# Sheet1.net
KiCad netlist of a schematic drawn in Altium Designer
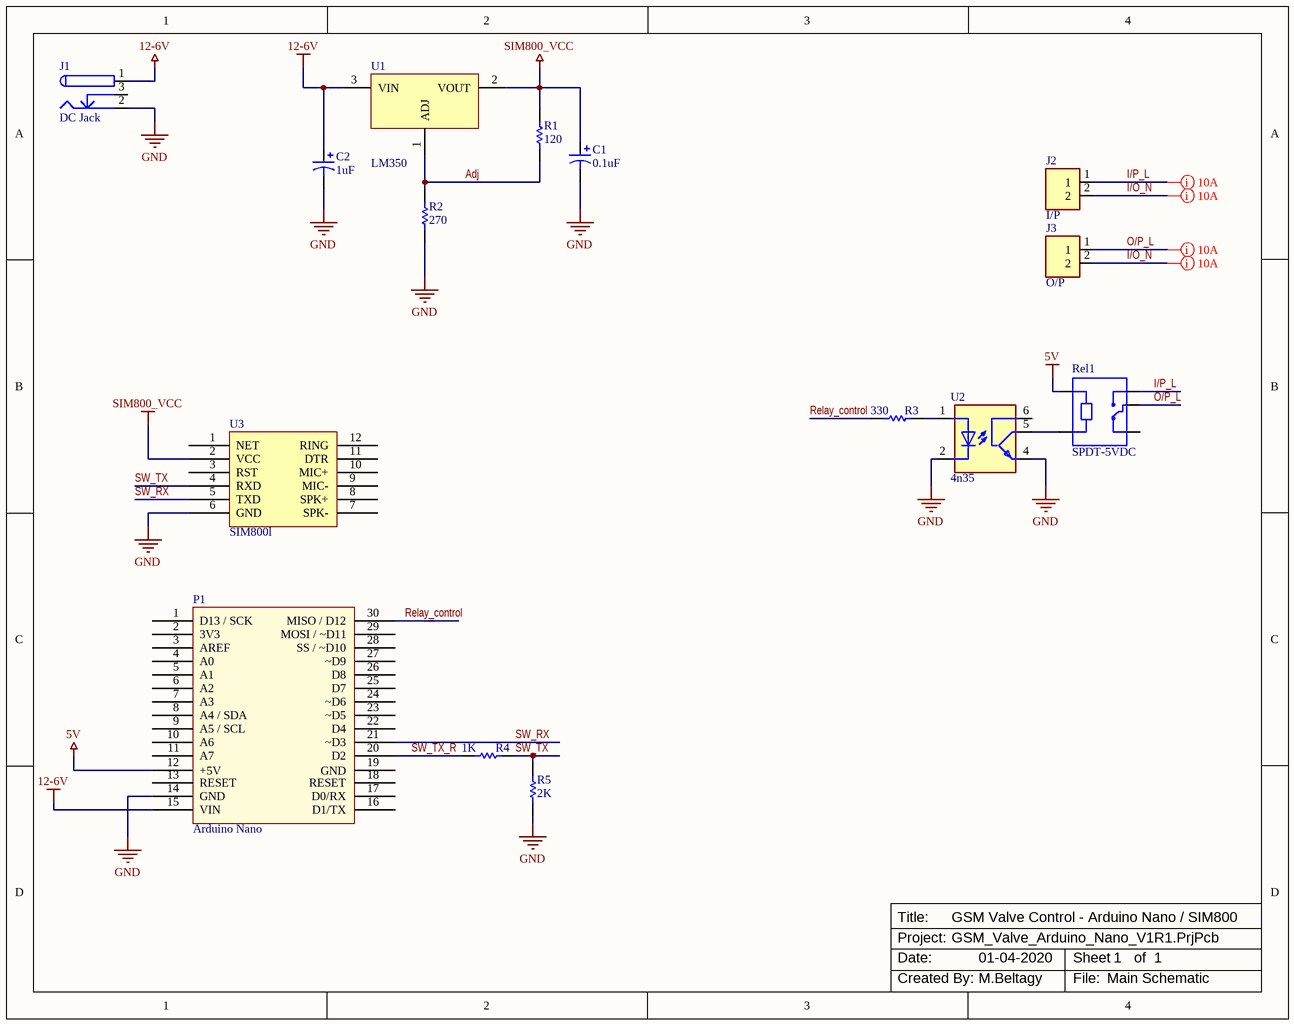
[diagram p0: Sheet1.SchDoc]

(export (version "E")
  (design (tool "Eeschema 10.0.6"))
  (components
    (comp (ref "C1")
      (value "0.1uF")
      (footprint "R38")
      (description "Polarized Capacitor (Radial)")
      (fields (field (name "PUBLISHER") "Altium Limited"))
      (libsource (lib "Miscellaneous Devices") (part "Cap Pol1"))
    )
    (comp (ref "C2")
      (value "1uF")
      (footprint "R38")
      (description "Polarized Capacitor (Radial)")
      (fields (field (name "PUBLISHER") "Altium Limited"))
      (libsource (lib "Miscellaneous Devices") (part "Cap Pol1"))
    )
    (comp (ref "J1")
      (value "DC Jack")
      (footprint "DC Jack - KLDHCX")
      (fields
        (field (name "MANUFACTURER") "Kycon")
        (field (name "MANUFACTURER PART NUMBER") "KLDHCX-0202-AC-1")
      )
      (libsource (lib "Belle_library") (part "DC Jack"))
    )
    (comp (ref "J2")
      (value "I/P")
      (footprint "Terminal Block - 2")
      (description "Terminal Block - 2 Positions")
      (fields
        (field (name "MANUFACTURER") "CUI")
        (field (name "MANUFACTURER PART NUMBER") "TBP01P1-508-02BE")
      )
      (libsource (lib "Belle_library") (part "TBP01P1-508-02BE"))
    )
    (comp (ref "J3")
      (value "O/P")
      (footprint "Terminal Block - 2")
      (description "Terminal Block - 2 Positions")
      (fields
        (field (name "MANUFACTURER") "CUI")
        (field (name "MANUFACTURER PART NUMBER") "TBP01P1-508-02BE")
      )
      (libsource (lib "Belle_library") (part "TBP01P1-508-02BE"))
    )
    (comp (ref "P1")
      (value "Arduino Nano")
      (footprint "Arduino Nano")
      (fields (field (name "MANUFACTURER") "Arduino"))
      (libsource (lib "Arduino") (part "Arduino Nano"))
    )
    (comp (ref "R1")
      (value "120")
      (footprint "AXIAL-0.5")
      (description "Semiconductor Resistor")
      (libsource (lib "Miscellaneous Devices") (part "Res Semi"))
    )
    (comp (ref "R2")
      (value "270")
      (footprint "AXIAL-0.5")
      (description "Semiconductor Resistor")
      (libsource (lib "Miscellaneous Devices") (part "Res Semi"))
    )
    (comp (ref "R3")
      (value "330")
      (footprint "AXIAL-0.5")
      (description "Semiconductor Resistor")
      (libsource (lib "Miscellaneous Devices") (part "Res Semi"))
    )
    (comp (ref "R4")
      (value "1K")
      (footprint "AXIAL-0.5")
      (description "Semiconductor Resistor")
      (libsource (lib "Miscellaneous Devices") (part "Res Semi"))
    )
    (comp (ref "R5")
      (value "2K")
      (footprint "AXIAL-0.5")
      (description "Semiconductor Resistor")
      (libsource (lib "Miscellaneous Devices") (part "Res Semi"))
    )
    (comp (ref "Rel1")
      (value "SPDT-5VDC")
      (footprint "SRD-5VDC")
      (libsource (lib "Belle_library") (part "Relay-SRD-5VDC"))
    )
    (comp (ref "U1")
      (value "LM350")
      (footprint "TO254P1054X470X1955-3")
      (fields
        (field (name "MANUFACTURER") "TI National Semiconductor")
        (field (name "MANUFACTURER PART NUMBER") "LM350AT/NOPB")
      )
      (libsource (lib "Belle_library") (part "LM350"))
    )
    (comp (ref "U2")
      (value "4n35")
      (footprint "DIP6")
      (fields (field (name "MANUFACTURER") "Everlight") (field (name "MANUFACTURER PART NUMBER") "4N35"))
      (libsource (lib "Belle_library") (part "4N35"))
    )
    (comp (ref "U3")
      (value "SIM800l")
      (footprint "SIM800l")
      (fields (field (name "MANUFACTURER PART NUMBER") "SIM800l Breakout"))
      (libsource (lib "Belle_library") (part "SIM800l"))
    )
  )
  (nets
    (net (code "1") (name "/Adj") (class "Default")
      (node (ref "R1") (pin "1") (pinfunction "1_1") (pintype "passive"))
      (node (ref "R2") (pin "2") (pinfunction "2_2") (pintype "passive"))
      (node (ref "U1") (pin "1") (pinfunction "ADJ_1") (pintype "power_in"))
    )
    (net (code "2") (name "/I{slash}O_N") (class "Default")
      (node (ref "J2") (pin "2") (pinfunction "2_2") (pintype "passive"))
      (node (ref "J3") (pin "2") (pinfunction "2_2") (pintype "passive"))
    )
    (net (code "3") (name "/I{slash}P_L") (class "Default")
      (node (ref "J2") (pin "1") (pinfunction "1_1") (pintype "passive"))
      (node (ref "Rel1") (pin "NO") (pinfunction "NO_NO") (pintype "passive"))
    )
    (net (code "4") (name "/O{slash}P_L") (class "Default")
      (node (ref "J3") (pin "1") (pinfunction "1_1") (pintype "passive"))
      (node (ref "Rel1") (pin "COM") (pinfunction "COM_COM") (pintype "passive"))
    )
    (net (code "5") (name "/Relay_control") (class "Default")
      (node (ref "P1") (pin "30") (pinfunction "MISO_/_D12_30") (pintype "passive"))
      (node (ref "R3") (pin "1") (pinfunction "1_1") (pintype "passive"))
    )
    (net (code "6") (name "/SW_RX") (class "Default")
      (node (ref "P1") (pin "21") (pinfunction "~D3_21") (pintype "passive"))
      (node (ref "U3") (pin "5") (pinfunction "TXD_5") (pintype "passive"))
    )
    (net (code "7") (name "/SW_TX") (class "Default")
      (node (ref "R4") (pin "2") (pinfunction "2_2") (pintype "passive"))
      (node (ref "R5") (pin "2") (pinfunction "2_2") (pintype "passive"))
      (node (ref "U3") (pin "4") (pinfunction "RXD_4") (pintype "passive"))
    )
    (net (code "8") (name "/SW_TX_R") (class "Default")
      (node (ref "P1") (pin "20") (pinfunction "D2_20") (pintype "passive"))
      (node (ref "R4") (pin "1") (pinfunction "1_1") (pintype "passive"))
    )
    (net (code "9") (name "5V") (class "Default")
      (node (ref "P1") (pin "12") (pinfunction "+5V_12") (pintype "passive"))
      (node (ref "Rel1") (pin "A1") (pinfunction "A1_A1") (pintype "passive"))
    )
    (net (code "10") (name "12-6V") (class "Default")
      (node (ref "C2") (pin "1") (pinfunction "1_1") (pintype "passive"))
      (node (ref "J1") (pin "1") (pinfunction "1_1") (pintype "power_in"))
      (node (ref "P1") (pin "15") (pinfunction "VIN_15") (pintype "passive"))
      (node (ref "U1") (pin "3") (pinfunction "VIN_3") (pintype "power_in"))
    )
    (net (code "11") (name "GND") (class "Default")
      (node (ref "C1") (pin "2") (pinfunction "2_2") (pintype "passive"))
      (node (ref "C2") (pin "2") (pinfunction "2_2") (pintype "passive"))
      (node (ref "J1") (pin "2") (pinfunction "2_2") (pintype "power_in"))
      (node (ref "P1") (pin "14") (pinfunction "GND_14") (pintype "passive"))
      (node (ref "R2") (pin "1") (pinfunction "1_1") (pintype "passive"))
      (node (ref "R5") (pin "1") (pinfunction "1_1") (pintype "passive"))
      (node (ref "U2") (pin "2") (pinfunction "C_2") (pintype "passive"))
      (node (ref "U2") (pin "4") (pinfunction "EMI_4") (pintype "passive"))
      (node (ref "U3") (pin "6") (pinfunction "GND_6") (pintype "passive"))
    )
    (net (code "12") (name "Net-(U2-A)") (class "Default")
      (node (ref "R3") (pin "2") (pinfunction "2_2") (pintype "passive"))
      (node (ref "U2") (pin "1") (pinfunction "A_1") (pintype "passive"))
    )
    (net (code "13") (name "Net-(U2-COL)") (class "Default")
      (node (ref "Rel1") (pin "A2") (pinfunction "A2_A2") (pintype "passive"))
      (node (ref "U2") (pin "5") (pinfunction "COL_5") (pintype "passive"))
    )
    (net (code "14") (name "SIM800_VCC") (class "Default")
      (node (ref "C1") (pin "1") (pinfunction "1_1") (pintype "passive"))
      (node (ref "R1") (pin "2") (pinfunction "2_2") (pintype "passive"))
      (node (ref "U1") (pin "2") (pinfunction "VOUT_2") (pintype "passive"))
      (node (ref "U3") (pin "2") (pinfunction "VCC_2") (pintype "passive"))
    )
    (net (code "15") (name "unconnected-(J1-Pad3)") (class "Default")
      (node (ref "J1") (pin "3") (pinfunction "3_3") (pintype "power_in"))
    )
    (net (code "16") (name "unconnected-(P1-3V3-Pad2)") (class "Default")
      (node (ref "P1") (pin "2") (pinfunction "3V3_2") (pintype "passive"))
    )
    (net (code "17") (name "unconnected-(P1-A0-Pad4)") (class "Default")
      (node (ref "P1") (pin "4") (pinfunction "A0_4") (pintype "passive"))
    )
    (net (code "18") (name "unconnected-(P1-A1-Pad5)") (class "Default")
      (node (ref "P1") (pin "5") (pinfunction "A1_5") (pintype "passive"))
    )
    (net (code "19") (name "unconnected-(P1-A2-Pad6)") (class "Default")
      (node (ref "P1") (pin "6") (pinfunction "A2_6") (pintype "passive"))
    )
    (net (code "20") (name "unconnected-(P1-A3-Pad7)") (class "Default")
      (node (ref "P1") (pin "7") (pinfunction "A3_7") (pintype "passive"))
    )
    (net (code "21") (name "unconnected-(P1-A4_{slash}_SDA-Pad8)") (class "Default")
      (node (ref "P1") (pin "8") (pinfunction "A4_/_SDA_8") (pintype "passive"))
    )
    (net (code "22") (name "unconnected-(P1-A5_{slash}_SCL-Pad9)") (class "Default")
      (node (ref "P1") (pin "9") (pinfunction "A5_/_SCL_9") (pintype "passive"))
    )
    (net (code "23") (name "unconnected-(P1-A6-Pad10)") (class "Default")
      (node (ref "P1") (pin "10") (pinfunction "A6_10") (pintype "passive"))
    )
    (net (code "24") (name "unconnected-(P1-A7-Pad11)") (class "Default")
      (node (ref "P1") (pin "11") (pinfunction "A7_11") (pintype "passive"))
    )
    (net (code "25") (name "unconnected-(P1-AREF-Pad3)") (class "Default")
      (node (ref "P1") (pin "3") (pinfunction "AREF_3") (pintype "passive"))
    )
    (net (code "26") (name "unconnected-(P1-D0{slash}RX-Pad17)") (class "Default")
      (node (ref "P1") (pin "17") (pinfunction "D0/RX_17") (pintype "passive"))
    )
    (net (code "27") (name "unconnected-(P1-D1{slash}TX-Pad16)") (class "Default")
      (node (ref "P1") (pin "16") (pinfunction "D1/TX_16") (pintype "passive"))
    )
    (net (code "28") (name "unconnected-(P1-D4-Pad22)") (class "Default")
      (node (ref "P1") (pin "22") (pinfunction "D4_22") (pintype "passive"))
    )
    (net (code "29") (name "unconnected-(P1-D7-Pad25)") (class "Default")
      (node (ref "P1") (pin "25") (pinfunction "D7_25") (pintype "passive"))
    )
    (net (code "30") (name "unconnected-(P1-D8-Pad26)") (class "Default")
      (node (ref "P1") (pin "26") (pinfunction "D8_26") (pintype "passive"))
    )
    (net (code "31") (name "unconnected-(P1-D13_{slash}_SCK-Pad1)") (class "Default")
      (node (ref "P1") (pin "1") (pinfunction "D13_/_SCK_1") (pintype "passive"))
    )
    (net (code "32") (name "unconnected-(P1-GND-Pad19)") (class "Default")
      (node (ref "P1") (pin "19") (pinfunction "GND_19") (pintype "passive"))
    )
    (net (code "33") (name "unconnected-(P1-MOSI_{slash}_~D11-Pad29)") (class "Default")
      (node (ref "P1") (pin "29") (pinfunction "MOSI_/_~D11_29") (pintype "passive"))
    )
    (net (code "34") (name "unconnected-(P1-RESET-Pad13)") (class "Default")
      (node (ref "P1") (pin "13") (pinfunction "RESET_13") (pintype "passive"))
    )
    (net (code "35") (name "unconnected-(P1-RESET-Pad18)") (class "Default")
      (node (ref "P1") (pin "18") (pinfunction "RESET_18") (pintype "passive"))
    )
    (net (code "36") (name "unconnected-(P1-SS_{slash}_~D10-Pad28)") (class "Default")
      (node (ref "P1") (pin "28") (pinfunction "SS_/_~D10_28") (pintype "passive"))
    )
    (net (code "37") (name "unconnected-(P1-~D5-Pad23)") (class "Default")
      (node (ref "P1") (pin "23") (pinfunction "~D5_23") (pintype "passive"))
    )
    (net (code "38") (name "unconnected-(P1-~D6-Pad24)") (class "Default")
      (node (ref "P1") (pin "24") (pinfunction "~D6_24") (pintype "passive"))
    )
    (net (code "39") (name "unconnected-(P1-~D9-Pad27)") (class "Default")
      (node (ref "P1") (pin "27") (pinfunction "~D9_27") (pintype "passive"))
    )
    (net (code "40") (name "unconnected-(Rel1-PadNC)") (class "Default")
      (node (ref "Rel1") (pin "NC") (pinfunction "NC_NC") (pintype "passive"))
    )
    (net (code "41") (name "unconnected-(U2-BAS-Pad6)") (class "Default")
      (node (ref "U2") (pin "6") (pinfunction "BAS_6") (pintype "passive"))
    )
    (net (code "42") (name "unconnected-(U3-DTR-Pad11)") (class "Default")
      (node (ref "U3") (pin "11") (pinfunction "DTR_11") (pintype "passive"))
    )
    (net (code "43") (name "unconnected-(U3-MIC+-Pad10)") (class "Default")
      (node (ref "U3") (pin "10") (pinfunction "MIC+_10") (pintype "passive"))
    )
    (net (code "44") (name "unconnected-(U3-MIC--Pad9)") (class "Default")
      (node (ref "U3") (pin "9") (pinfunction "MIC-_9") (pintype "passive"))
    )
    (net (code "45") (name "unconnected-(U3-NET-Pad1)") (class "Default")
      (node (ref "U3") (pin "1") (pinfunction "NET_1") (pintype "passive"))
    )
    (net (code "46") (name "unconnected-(U3-RING-Pad12)") (class "Default")
      (node (ref "U3") (pin "12") (pinfunction "RING_12") (pintype "passive"))
    )
    (net (code "47") (name "unconnected-(U3-RST-Pad3)") (class "Default")
      (node (ref "U3") (pin "3") (pinfunction "RST_3") (pintype "passive"))
    )
    (net (code "48") (name "unconnected-(U3-SPK+-Pad8)") (class "Default")
      (node (ref "U3") (pin "8") (pinfunction "SPK+_8") (pintype "passive"))
    )
    (net (code "49") (name "unconnected-(U3-SPK--Pad7)") (class "Default")
      (node (ref "U3") (pin "7") (pinfunction "SPK-_7") (pintype "passive"))
    )
  )
)
